# spt_interface_v5_withbattcheck.net
KiCad netlist of a schematic drawn in EAGLE
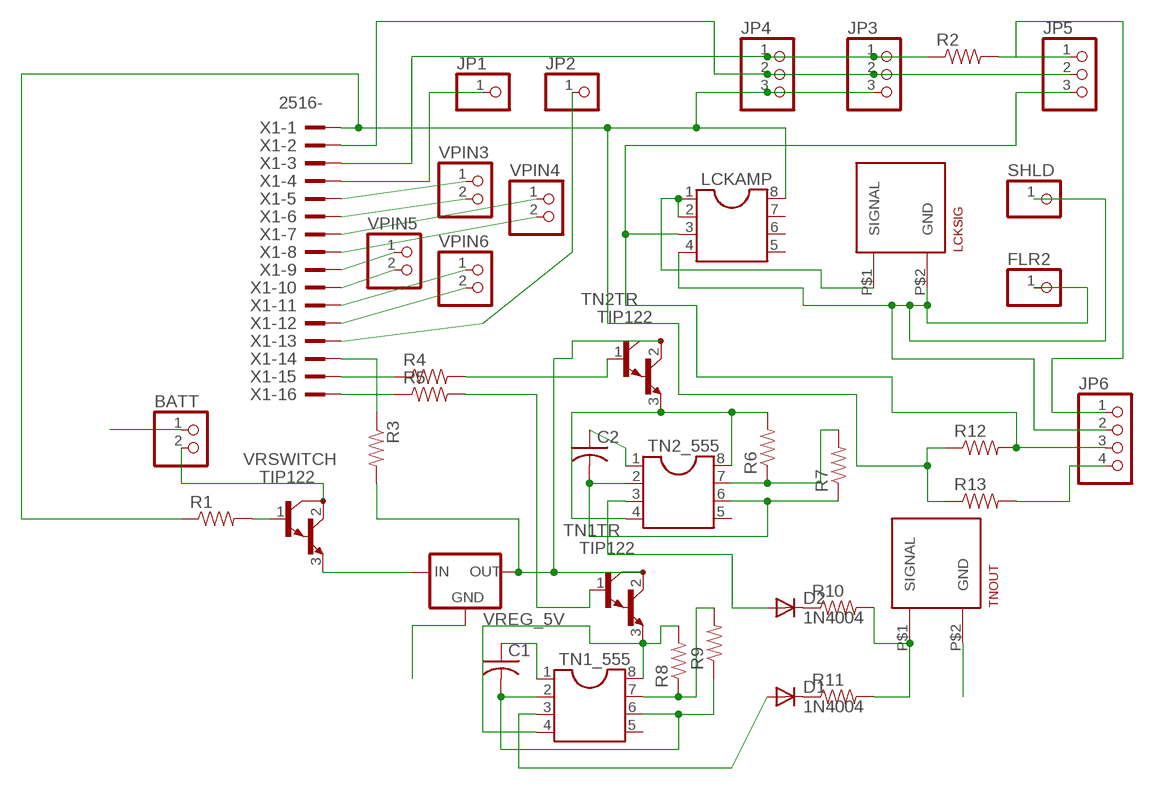
[diagram p0: schematic, sheet 1]

(export (version "E")
  (design (tool "Eeschema 10.0.6"))
  (components
    (comp (ref "BATT")
      (value "PINHD-1X2")
      (footprint "eagle-import:1X02")
      (libsource (lib "eagle-import") (part "PINHD-1X2"))
    )
    (comp (ref "C1")
      (value "C-US050-024X044")
      (footprint "eagle-import:C050-024X044")
      (libsource (lib "eagle-import") (part "C-US050-024X044"))
    )
    (comp (ref "C2")
      (value "C-US050-024X044")
      (footprint "eagle-import:C050-024X044")
      (libsource (lib "eagle-import") (part "C-US050-024X044"))
    )
    (comp (ref "D1")
      (value "1N4004")
      (footprint "eagle-import:DO41-10")
      (libsource (lib "eagle-import") (part "1N4004"))
    )
    (comp (ref "D2")
      (value "1N4004")
      (footprint "eagle-import:DO41-10")
      (libsource (lib "eagle-import") (part "1N4004"))
    )
    (comp (ref "FLR2")
      (value "PINHD-1X1")
      (footprint "eagle-import:1X01")
      (libsource (lib "eagle-import") (part "PINHD-1X1"))
    )
    (comp (ref "JP1")
      (value "PINHD-1X1")
      (footprint "eagle-import:1X01")
      (libsource (lib "eagle-import") (part "PINHD-1X1"))
    )
    (comp (ref "JP2")
      (value "PINHD-1X1")
      (footprint "eagle-import:1X01")
      (libsource (lib "eagle-import") (part "PINHD-1X1"))
    )
    (comp (ref "JP3")
      (value "PINHD-1X3")
      (footprint "eagle-import:1X03")
      (libsource (lib "eagle-import") (part "PINHD-1X3"))
    )
    (comp (ref "JP4")
      (value "PINHD-1X3")
      (footprint "eagle-import:1X03")
      (libsource (lib "eagle-import") (part "PINHD-1X3"))
    )
    (comp (ref "JP5")
      (value "PINHD-1X3")
      (footprint "eagle-import:1X03")
      (libsource (lib "eagle-import") (part "PINHD-1X3"))
    )
    (comp (ref "JP6")
      (value "PINHD-1X4")
      (footprint "eagle-import:1X04")
      (libsource (lib "eagle-import") (part "PINHD-1X4"))
    )
    (comp (ref "LCKAMP")
      (value "DIL8")
      (footprint "eagle-import:DIL08")
      (libsource (lib "eagle-import") (part "DIL8"))
    )
    (comp (ref "LCKSIG")
      (value "BNC_VERTICAL")
      (footprint "eagle-import:BNC_VERTICAL")
      (libsource (lib "eagle-import") (part "BNC_VERTICAL"))
    )
    (comp (ref "R1")
      (value "1KOHM-1/4W-5%(PTH)HORIZ-KIT")
      (footprint "eagle-import:AXIAL-0.3EZ")
      (libsource (lib "eagle-import") (part "1KOHM-1/4W-5%(PTH)HORIZ-KIT"))
    )
    (comp (ref "R2")
      (value "1KOHM-1/4W-5%(PTH)HORIZ-KIT")
      (footprint "eagle-import:AXIAL-0.3EZ")
      (libsource (lib "eagle-import") (part "1KOHM-1/4W-5%(PTH)HORIZ-KIT"))
    )
    (comp (ref "R3")
      (value "1KOHM-1/4W-5%(PTH)HORIZ-KIT")
      (footprint "eagle-import:AXIAL-0.3EZ")
      (libsource (lib "eagle-import") (part "1KOHM-1/4W-5%(PTH)HORIZ-KIT"))
    )
    (comp (ref "R4")
      (value "1KOHM-1/4W-5%(PTH)HORIZ-KIT")
      (footprint "eagle-import:AXIAL-0.3EZ")
      (libsource (lib "eagle-import") (part "1KOHM-1/4W-5%(PTH)HORIZ-KIT"))
    )
    (comp (ref "R5")
      (value "1KOHM-1/4W-5%(PTH)HORIZ-KIT")
      (footprint "eagle-import:AXIAL-0.3EZ")
      (libsource (lib "eagle-import") (part "1KOHM-1/4W-5%(PTH)HORIZ-KIT"))
    )
    (comp (ref "R6")
      (value "1KOHM-1/4W-5%(PTH)HORIZ-KIT")
      (footprint "eagle-import:AXIAL-0.3EZ")
      (libsource (lib "eagle-import") (part "1KOHM-1/4W-5%(PTH)HORIZ-KIT"))
    )
    (comp (ref "R7")
      (value "1KOHM-1/4W-5%(PTH)HORIZ-KIT")
      (footprint "eagle-import:AXIAL-0.3EZ")
      (libsource (lib "eagle-import") (part "1KOHM-1/4W-5%(PTH)HORIZ-KIT"))
    )
    (comp (ref "R8")
      (value "1KOHM-1/4W-5%(PTH)HORIZ-KIT")
      (footprint "eagle-import:AXIAL-0.3EZ")
      (libsource (lib "eagle-import") (part "1KOHM-1/4W-5%(PTH)HORIZ-KIT"))
    )
    (comp (ref "R9")
      (value "1KOHM-1/4W-5%(PTH)HORIZ-KIT")
      (footprint "eagle-import:AXIAL-0.3EZ")
      (libsource (lib "eagle-import") (part "1KOHM-1/4W-5%(PTH)HORIZ-KIT"))
    )
    (comp (ref "R10")
      (value "1KOHM-1/4W-5%(PTH)HORIZ-KIT")
      (footprint "eagle-import:AXIAL-0.3EZ")
      (libsource (lib "eagle-import") (part "1KOHM-1/4W-5%(PTH)HORIZ-KIT"))
    )
    (comp (ref "R11")
      (value "1KOHM-1/4W-5%(PTH)HORIZ-KIT")
      (footprint "eagle-import:AXIAL-0.3EZ")
      (libsource (lib "eagle-import") (part "1KOHM-1/4W-5%(PTH)HORIZ-KIT"))
    )
    (comp (ref "R12")
      (value "1KOHM-1/4W-5%(PTH)HORIZ-KIT")
      (footprint "eagle-import:AXIAL-0.3EZ")
      (libsource (lib "eagle-import") (part "1KOHM-1/4W-5%(PTH)HORIZ-KIT"))
    )
    (comp (ref "R13")
      (value "1KOHM-1/4W-5%(PTH)HORIZ-KIT")
      (footprint "eagle-import:AXIAL-0.3EZ")
      (libsource (lib "eagle-import") (part "1KOHM-1/4W-5%(PTH)HORIZ-KIT"))
    )
    (comp (ref "SHLD")
      (value "PINHD-1X1")
      (footprint "eagle-import:1X01")
      (libsource (lib "eagle-import") (part "PINHD-1X1"))
    )
    (comp (ref "TN1TR")
      (value "TIP122")
      (footprint "eagle-import:TO220")
      (libsource (lib "eagle-import") (part "TIP122"))
    )
    (comp (ref "TN1_555")
      (value "DIL8")
      (footprint "eagle-import:DIL08")
      (libsource (lib "eagle-import") (part "DIL8"))
    )
    (comp (ref "TN2TR")
      (value "TIP122")
      (footprint "eagle-import:TO220")
      (libsource (lib "eagle-import") (part "TIP122"))
    )
    (comp (ref "TN2_555")
      (value "DIL8")
      (footprint "eagle-import:DIL08")
      (libsource (lib "eagle-import") (part "DIL8"))
    )
    (comp (ref "TNOUT")
      (value "BNC_VERTICAL")
      (footprint "eagle-import:BNC_VERTICAL")
      (libsource (lib "eagle-import") (part "BNC_VERTICAL"))
    )
    (comp (ref "VPIN3")
      (value "PINHD-1X2")
      (footprint "eagle-import:1X02")
      (libsource (lib "eagle-import") (part "PINHD-1X2"))
    )
    (comp (ref "VPIN4")
      (value "PINHD-1X2")
      (footprint "eagle-import:1X02")
      (libsource (lib "eagle-import") (part "PINHD-1X2"))
    )
    (comp (ref "VPIN5")
      (value "PINHD-1X2")
      (footprint "eagle-import:1X02")
      (libsource (lib "eagle-import") (part "PINHD-1X2"))
    )
    (comp (ref "VPIN6")
      (value "PINHD-1X2")
      (footprint "eagle-import:1X02")
      (libsource (lib "eagle-import") (part "PINHD-1X2"))
    )
    (comp (ref "VREG_5V")
      (value "78XXL")
      (footprint "eagle-import:78XXL")
      (libsource (lib "eagle-import") (part "78XXL"))
    )
    (comp (ref "VRSWITCH")
      (value "TIP122")
      (footprint "eagle-import:TO220")
      (libsource (lib "eagle-import") (part "TIP122"))
    )
    (comp (ref "X1")
      (value "2516-")
      (footprint "eagle-import:PAK100_2500-16")
      (libsource (lib "eagle-import") (part "2516-"))
    )
  )
  (nets
    (net (code "1") (name "/GND") (class "Default")
      (node (ref "BATT") (pin "1") (pinfunction "1_1") (pintype "passive"))
      (node (ref "C1") (pin "1") (pinfunction "1_1") (pintype "passive"))
      (node (ref "C2") (pin "1") (pinfunction "1_1") (pintype "passive"))
      (node (ref "FLR2") (pin "1") (pinfunction "1_1") (pintype "passive"))
      (node (ref "JP3") (pin "2") (pinfunction "2_2") (pintype "passive"))
      (node (ref "JP4") (pin "2") (pinfunction "2_2") (pintype "passive"))
      (node (ref "JP5") (pin "2") (pinfunction "2_2") (pintype "passive"))
      (node (ref "JP6") (pin "2") (pinfunction "2_2") (pintype "passive"))
      (node (ref "LCKAMP") (pin "4") (pinfunction "4_4") (pintype "passive"))
      (node (ref "LCKSIG") (pin "P$2") (pinfunction "GND_P$2") (pintype "bidirectional"))
      (node (ref "SHLD") (pin "1") (pinfunction "1_1") (pintype "passive"))
      (node (ref "TN1_555") (pin "1") (pinfunction "1_1") (pintype "passive"))
      (node (ref "TN2_555") (pin "1") (pinfunction "1_1") (pintype "passive"))
      (node (ref "TNOUT") (pin "P$2") (pinfunction "GND_P$2") (pintype "bidirectional"))
      (node (ref "VREG_5V") (pin "GND") (pinfunction "GND_GND") (pintype "input"))
      (node (ref "X1") (pin "2") (pinfunction "KL_2") (pintype "passive"))
    )
    (net (code "2") (name "Net-(D1-PadA)") (class "Default")
      (node (ref "D1") (pin "A") (pinfunction "A_A") (pintype "passive"))
      (node (ref "TN1_555") (pin "3") (pinfunction "3_3") (pintype "passive"))
    )
    (net (code "3") (name "Net-(D2-PadA)") (class "Default")
      (node (ref "D2") (pin "A") (pinfunction "A_A") (pintype "passive"))
      (node (ref "TN2_555") (pin "3") (pinfunction "3_3") (pintype "passive"))
    )
    (net (code "4") (name "Net-(LCKSIG-SIGNAL)") (class "Default")
      (node (ref "LCKAMP") (pin "1") (pinfunction "1_1") (pintype "passive"))
      (node (ref "LCKAMP") (pin "2") (pinfunction "2_2") (pintype "passive"))
      (node (ref "LCKSIG") (pin "P$1") (pinfunction "SIGNAL_P$1") (pintype "bidirectional"))
    )
    (net (code "5") (name "Net-(R1-1)") (class "Default")
      (node (ref "JP3") (pin "3") (pinfunction "3_3") (pintype "passive"))
      (node (ref "JP4") (pin "3") (pinfunction "3_3") (pintype "passive"))
      (node (ref "LCKAMP") (pin "8") (pinfunction "8_8") (pintype "passive"))
      (node (ref "R1") (pin "P$1") (pinfunction "1_P$1") (pintype "passive"))
      (node (ref "R12") (pin "P$1") (pinfunction "1_P$1") (pintype "passive"))
      (node (ref "R13") (pin "P$1") (pinfunction "1_P$1") (pintype "passive"))
      (node (ref "X1") (pin "1") (pinfunction "KL_1") (pintype "passive"))
    )
    (net (code "6") (name "Net-(R1-2)") (class "Default")
      (node (ref "R1") (pin "P$2") (pinfunction "2_P$2") (pintype "passive"))
      (node (ref "VRSWITCH") (pin "1") (pinfunction "B_1") (pintype "passive"))
    )
    (net (code "7") (name "Net-(R2-1)") (class "Default")
      (node (ref "JP3") (pin "1") (pinfunction "1_1") (pintype "passive"))
      (node (ref "JP4") (pin "1") (pinfunction "1_1") (pintype "passive"))
      (node (ref "R2") (pin "P$1") (pinfunction "1_P$1") (pintype "passive"))
      (node (ref "X1") (pin "3") (pinfunction "KL_3") (pintype "passive"))
    )
    (net (code "8") (name "Net-(R2-2)") (class "Default")
      (node (ref "JP5") (pin "1") (pinfunction "1_1") (pintype "passive"))
      (node (ref "JP6") (pin "1") (pinfunction "1_1") (pintype "passive"))
      (node (ref "R2") (pin "P$2") (pinfunction "2_P$2") (pintype "passive"))
    )
    (net (code "9") (name "Net-(R3-1)") (class "Default")
      (node (ref "R3") (pin "P$1") (pinfunction "1_P$1") (pintype "passive"))
      (node (ref "X1") (pin "14") (pinfunction "KL_14") (pintype "passive"))
    )
    (net (code "10") (name "Net-(R3-2)") (class "Default")
      (node (ref "R3") (pin "P$2") (pinfunction "2_P$2") (pintype "passive"))
      (node (ref "TN1TR") (pin "2") (pinfunction "C_2") (pintype "passive"))
      (node (ref "TN2TR") (pin "2") (pinfunction "C_2") (pintype "passive"))
      (node (ref "VREG_5V") (pin "OUT") (pinfunction "OUT_OUT") (pintype "passive"))
    )
    (net (code "11") (name "Net-(R4-1)") (class "Default")
      (node (ref "R4") (pin "P$1") (pinfunction "1_P$1") (pintype "passive"))
      (node (ref "X1") (pin "15") (pinfunction "KL_15") (pintype "passive"))
    )
    (net (code "12") (name "Net-(R4-2)") (class "Default")
      (node (ref "R4") (pin "P$2") (pinfunction "2_P$2") (pintype "passive"))
      (node (ref "TN2TR") (pin "1") (pinfunction "B_1") (pintype "passive"))
    )
    (net (code "13") (name "Net-(R5-1)") (class "Default")
      (node (ref "R5") (pin "P$1") (pinfunction "1_P$1") (pintype "passive"))
      (node (ref "X1") (pin "16") (pinfunction "KL_16") (pintype "passive"))
    )
    (net (code "14") (name "Net-(R5-2)") (class "Default")
      (node (ref "R5") (pin "P$2") (pinfunction "2_P$2") (pintype "passive"))
      (node (ref "TN1TR") (pin "1") (pinfunction "B_1") (pintype "passive"))
    )
    (net (code "15") (name "Net-(R6-1)") (class "Default")
      (node (ref "R6") (pin "P$1") (pinfunction "1_P$1") (pintype "passive"))
      (node (ref "R7") (pin "P$2") (pinfunction "2_P$2") (pintype "passive"))
      (node (ref "TN2_555") (pin "7") (pinfunction "7_7") (pintype "passive"))
    )
    (net (code "16") (name "Net-(R6-2)") (class "Default")
      (node (ref "R6") (pin "P$2") (pinfunction "2_P$2") (pintype "passive"))
      (node (ref "TN2TR") (pin "3") (pinfunction "E_3") (pintype "passive"))
      (node (ref "TN2_555") (pin "4") (pinfunction "4_4") (pintype "passive"))
      (node (ref "TN2_555") (pin "8") (pinfunction "8_8") (pintype "passive"))
    )
    (net (code "17") (name "Net-(R7-1)") (class "Default")
      (node (ref "C2") (pin "2") (pinfunction "2_2") (pintype "passive"))
      (node (ref "R7") (pin "P$1") (pinfunction "1_P$1") (pintype "passive"))
      (node (ref "TN2_555") (pin "2") (pinfunction "2_2") (pintype "passive"))
      (node (ref "TN2_555") (pin "6") (pinfunction "6_6") (pintype "passive"))
    )
    (net (code "18") (name "Net-(R8-1)") (class "Default")
      (node (ref "R8") (pin "P$1") (pinfunction "1_P$1") (pintype "passive"))
      (node (ref "R9") (pin "P$2") (pinfunction "2_P$2") (pintype "passive"))
      (node (ref "TN1_555") (pin "7") (pinfunction "7_7") (pintype "passive"))
    )
    (net (code "19") (name "Net-(R8-2)") (class "Default")
      (node (ref "R8") (pin "P$2") (pinfunction "2_P$2") (pintype "passive"))
      (node (ref "TN1TR") (pin "3") (pinfunction "E_3") (pintype "passive"))
      (node (ref "TN1_555") (pin "4") (pinfunction "4_4") (pintype "passive"))
      (node (ref "TN1_555") (pin "8") (pinfunction "8_8") (pintype "passive"))
    )
    (net (code "20") (name "Net-(R9-1)") (class "Default")
      (node (ref "C1") (pin "2") (pinfunction "2_2") (pintype "passive"))
      (node (ref "R9") (pin "P$1") (pinfunction "1_P$1") (pintype "passive"))
      (node (ref "TN1_555") (pin "2") (pinfunction "2_2") (pintype "passive"))
      (node (ref "TN1_555") (pin "6") (pinfunction "6_6") (pintype "passive"))
    )
    (net (code "21") (name "Net-(R10-1)") (class "Default")
      (node (ref "D2") (pin "C") (pinfunction "C_C") (pintype "passive"))
      (node (ref "R10") (pin "P$1") (pinfunction "1_P$1") (pintype "passive"))
    )
    (net (code "22") (name "Net-(R10-2)") (class "Default")
      (node (ref "R10") (pin "P$2") (pinfunction "2_P$2") (pintype "passive"))
      (node (ref "R11") (pin "P$2") (pinfunction "2_P$2") (pintype "passive"))
      (node (ref "TNOUT") (pin "P$1") (pinfunction "SIGNAL_P$1") (pintype "bidirectional"))
    )
    (net (code "23") (name "Net-(R11-1)") (class "Default")
      (node (ref "D1") (pin "C") (pinfunction "C_C") (pintype "passive"))
      (node (ref "R11") (pin "P$1") (pinfunction "1_P$1") (pintype "passive"))
    )
    (net (code "24") (name "Net-(R12-2)") (class "Default")
      (node (ref "JP5") (pin "3") (pinfunction "3_3") (pintype "passive"))
      (node (ref "JP6") (pin "3") (pinfunction "3_3") (pintype "passive"))
      (node (ref "LCKAMP") (pin "3") (pinfunction "3_3") (pintype "passive"))
      (node (ref "R12") (pin "P$2") (pinfunction "2_P$2") (pintype "passive"))
    )
    (net (code "25") (name "Net-(R13-2)") (class "Default")
      (node (ref "JP6") (pin "4") (pinfunction "4_4") (pintype "passive"))
      (node (ref "R13") (pin "P$2") (pinfunction "2_P$2") (pintype "passive"))
    )
    (net (code "26") (name "Net-(VRSWITCH-C)") (class "Default")
      (node (ref "BATT") (pin "2") (pinfunction "2_2") (pintype "passive"))
      (node (ref "VRSWITCH") (pin "2") (pinfunction "C_2") (pintype "passive"))
    )
    (net (code "27") (name "Net-(VRSWITCH-E)") (class "Default")
      (node (ref "VREG_5V") (pin "IN") (pinfunction "IN_IN") (pintype "input"))
      (node (ref "VRSWITCH") (pin "3") (pinfunction "E_3") (pintype "passive"))
    )
    (net (code "28") (name "Net-(X1B-KL)") (class "Default")
      (node (ref "VPIN5") (pin "2") (pinfunction "2_2") (pintype "passive"))
      (node (ref "X1") (pin "10") (pinfunction "KL_10") (pintype "passive"))
    )
    (net (code "29") (name "Net-(X1C-KL)") (class "Default")
      (node (ref "VPIN6") (pin "1") (pinfunction "1_1") (pintype "passive"))
      (node (ref "X1") (pin "11") (pinfunction "KL_11") (pintype "passive"))
    )
    (net (code "30") (name "Net-(X1D-KL)") (class "Default")
      (node (ref "VPIN6") (pin "2") (pinfunction "2_2") (pintype "passive"))
      (node (ref "X1") (pin "12") (pinfunction "KL_12") (pintype "passive"))
    )
    (net (code "31") (name "Net-(X1E-KL)") (class "Default")
      (node (ref "JP2") (pin "1") (pinfunction "1_1") (pintype "passive"))
      (node (ref "X1") (pin "13") (pinfunction "KL_13") (pintype "passive"))
    )
    (net (code "32") (name "Net-(X1K-KL)") (class "Default")
      (node (ref "JP1") (pin "1") (pinfunction "1_1") (pintype "passive"))
      (node (ref "X1") (pin "4") (pinfunction "KL_4") (pintype "passive"))
    )
    (net (code "33") (name "Net-(X1L-KL)") (class "Default")
      (node (ref "VPIN3") (pin "1") (pinfunction "1_1") (pintype "passive"))
      (node (ref "X1") (pin "5") (pinfunction "KL_5") (pintype "passive"))
    )
    (net (code "34") (name "Net-(X1M-KL)") (class "Default")
      (node (ref "VPIN3") (pin "2") (pinfunction "2_2") (pintype "passive"))
      (node (ref "X1") (pin "6") (pinfunction "KL_6") (pintype "passive"))
    )
    (net (code "35") (name "Net-(X1N-KL)") (class "Default")
      (node (ref "VPIN4") (pin "1") (pinfunction "1_1") (pintype "passive"))
      (node (ref "X1") (pin "7") (pinfunction "KL_7") (pintype "passive"))
    )
    (net (code "36") (name "Net-(X1O-KL)") (class "Default")
      (node (ref "VPIN4") (pin "2") (pinfunction "2_2") (pintype "passive"))
      (node (ref "X1") (pin "8") (pinfunction "KL_8") (pintype "passive"))
    )
    (net (code "37") (name "Net-(X1P-KL)") (class "Default")
      (node (ref "VPIN5") (pin "1") (pinfunction "1_1") (pintype "passive"))
      (node (ref "X1") (pin "9") (pinfunction "KL_9") (pintype "passive"))
    )
    (net (code "38") (name "unconnected-(LCKAMP-Pad5)") (class "Default")
      (node (ref "LCKAMP") (pin "5") (pinfunction "5_5") (pintype "passive"))
    )
    (net (code "39") (name "unconnected-(LCKAMP-Pad6)") (class "Default")
      (node (ref "LCKAMP") (pin "6") (pinfunction "6_6") (pintype "passive"))
    )
    (net (code "40") (name "unconnected-(LCKAMP-Pad7)") (class "Default")
      (node (ref "LCKAMP") (pin "7") (pinfunction "7_7") (pintype "passive"))
    )
    (net (code "41") (name "unconnected-(TN1_555-Pad5)") (class "Default")
      (node (ref "TN1_555") (pin "5") (pinfunction "5_5") (pintype "passive"))
    )
    (net (code "42") (name "unconnected-(TN2_555-Pad5)") (class "Default")
      (node (ref "TN2_555") (pin "5") (pinfunction "5_5") (pintype "passive"))
    )
  )
)
